# Mini-Ph0xx_00.net
KiCad netlist of a schematic drawn in Altium Designer
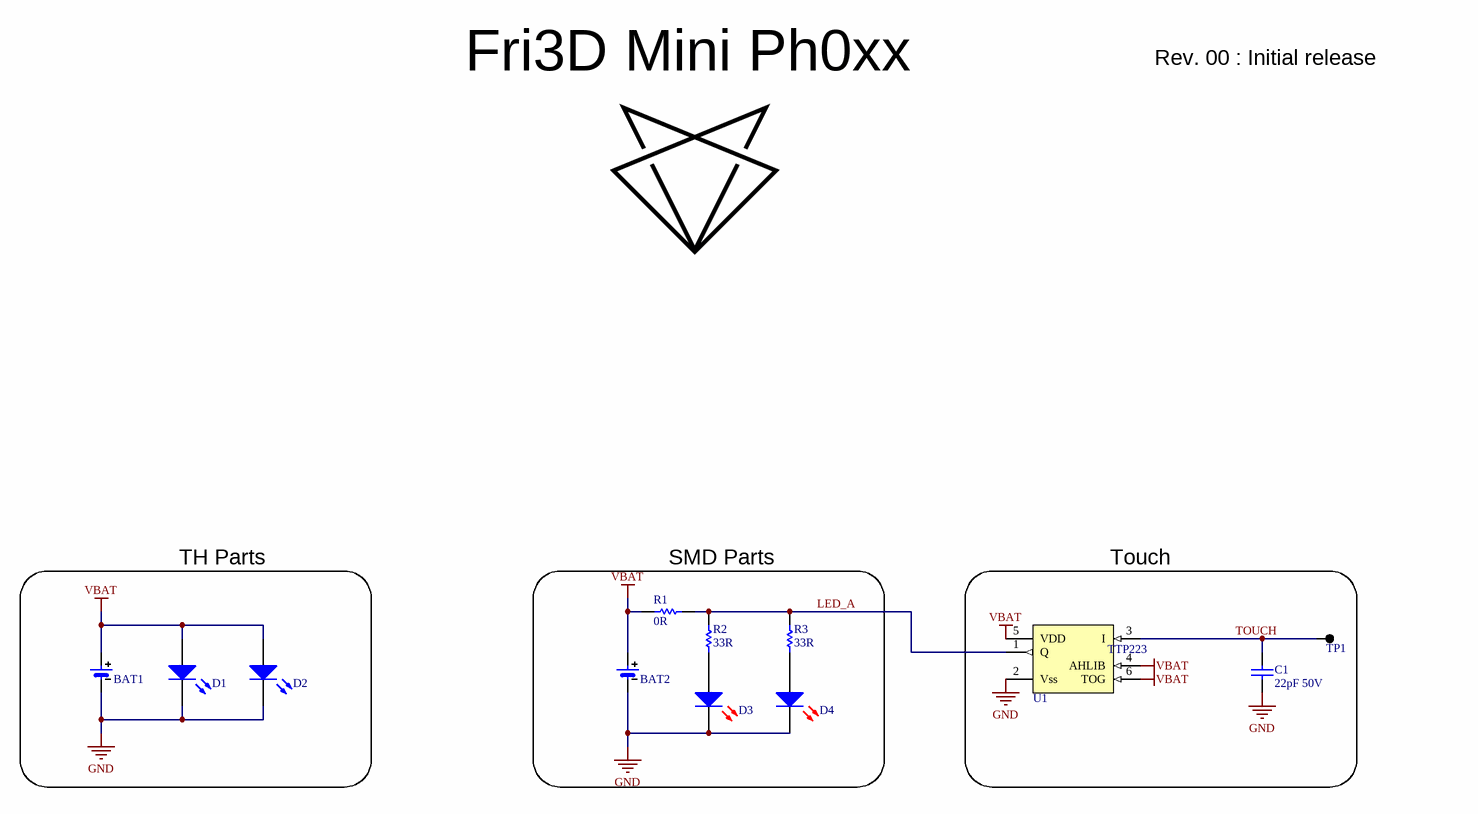
[diagram p0: Mini-Ph0xx_00.SchDoc]

(export (version "E")
  (design (tool "Eeschema 10.0.6"))
  (components
    (comp (ref "BAT1")
      (value "CR2032 Battery Holder")
      (footprint "BAT_CR2032")
      (description "=Description")
      (libsource (lib "Phyx_Components") (part "BAT_2"))
    )
    (comp (ref "BAT2")
      (value "CR2032 SMD Battery Holder")
      (footprint "BAT_CR2032_KEY_1060")
      (description "=Description")
      (libsource (lib "Phyx_Components") (part "BAT_2"))
    )
    (comp (ref "C1")
      (value "22pF 50V")
      (footprint "C1206_N")
      (description "Capacitor Ceramic")
      (fields (field (name "Comment") "CAP_CERAMIC"))
      (libsource (lib "Phyx_Components") (part "CAP_CERAMIC"))
    )
    (comp (ref "D1")
      (value "Default 5mm Blue LED")
      (footprint "LED_5MM_BL")
      (description "=Description")
      (libsource (lib "Phyx_Components") (part "LED_BLUE"))
    )
    (comp (ref "D2")
      (value "Default 5mm Blue LED")
      (footprint "LED_5MM_BL")
      (description "=Description")
      (libsource (lib "Phyx_Components") (part "LED_BLUE"))
    )
    (comp (ref "D3")
      (value "Default 0805 Red LED")
      (footprint "LED_0805_RD")
      (description "=Description")
      (libsource (lib "Phyx_Components") (part "LED_RED"))
    )
    (comp (ref "D4")
      (value "Default 0805 Red LED")
      (footprint "LED_0805_RD")
      (description "=Description")
      (libsource (lib "Phyx_Components") (part "LED_RED"))
    )
    (comp (ref "R1")
      (value "0R")
      (footprint "R1206")
      (fields (field (name "Comment") "RESISTOR"))
      (libsource (lib "Phyx_Components") (part "RESISTOR"))
    )
    (comp (ref "R2")
      (value "33R")
      (footprint "R1206")
      (fields (field (name "Comment") "RESISTOR"))
      (libsource (lib "Phyx_Components") (part "RESISTOR"))
    )
    (comp (ref "R3")
      (value "33R")
      (footprint "R1206")
      (fields (field (name "Comment") "RESISTOR"))
      (libsource (lib "Phyx_Components") (part "RESISTOR"))
    )
    (comp (ref "TP1")
      (value "TEST_PAD")
      (footprint "TP_0.8mm")
      (libsource (lib "Phyx_Components") (part "TEST_PAD"))
    )
    (comp (ref "U1")
      (value "Toggle dedicated touch IC")
      (footprint "SOT23-6")
      (description "=Description")
      (libsource (lib "Phyx_Components") (part "TTP223"))
    )
  )
  (nets
    (net (code "1") (name "/LED_A") (class "Default")
      (node (ref "R1") (pin "1") (pinfunction "1_1") (pintype "passive"))
      (node (ref "R2") (pin "1") (pinfunction "1_1") (pintype "passive"))
      (node (ref "R3") (pin "1") (pinfunction "1_1") (pintype "passive"))
      (node (ref "U1") (pin "1") (pinfunction "Q_1") (pintype "output"))
    )
    (net (code "2") (name "/TOUCH") (class "Default")
      (node (ref "C1") (pin "1") (pinfunction "1_1") (pintype "passive"))
      (node (ref "TP1") (pin "1") (pinfunction "1_1") (pintype "passive"))
      (node (ref "U1") (pin "3") (pinfunction "I_3") (pintype "input"))
    )
    (net (code "3") (name "GND") (class "Default")
      (node (ref "BAT1") (pin "2") (pinfunction "2_2") (pintype "passive"))
      (node (ref "BAT2") (pin "2") (pinfunction "2_2") (pintype "passive"))
      (node (ref "C1") (pin "2") (pinfunction "2_2") (pintype "passive"))
      (node (ref "D1") (pin "2") (pinfunction "K_2") (pintype "passive"))
      (node (ref "D2") (pin "2") (pinfunction "K_2") (pintype "passive"))
      (node (ref "D3") (pin "2") (pinfunction "K_2") (pintype "passive"))
      (node (ref "D4") (pin "2") (pinfunction "K_2") (pintype "passive"))
      (node (ref "U1") (pin "2") (pinfunction "Vss_2") (pintype "power_in"))
    )
    (net (code "4") (name "Net-(D3-A)") (class "Default")
      (node (ref "D3") (pin "1") (pinfunction "A_1") (pintype "passive"))
      (node (ref "R2") (pin "2") (pinfunction "2_2") (pintype "passive"))
    )
    (net (code "5") (name "Net-(D4-A)") (class "Default")
      (node (ref "D4") (pin "1") (pinfunction "A_1") (pintype "passive"))
      (node (ref "R3") (pin "2") (pinfunction "2_2") (pintype "passive"))
    )
    (net (code "6") (name "VBAT") (class "Default")
      (node (ref "BAT1") (pin "1") (pinfunction "1_1") (pintype "passive"))
      (node (ref "BAT2") (pin "1") (pinfunction "1_1") (pintype "passive"))
      (node (ref "D1") (pin "1") (pinfunction "A_1") (pintype "passive"))
      (node (ref "D2") (pin "1") (pinfunction "A_1") (pintype "passive"))
      (node (ref "R1") (pin "2") (pinfunction "2_2") (pintype "passive"))
      (node (ref "U1") (pin "4") (pinfunction "AHLIB_4") (pintype "input"))
      (node (ref "U1") (pin "5") (pinfunction "VDD_5") (pintype "power_in"))
      (node (ref "U1") (pin "6") (pinfunction "TOG_6") (pintype "input"))
    )
  )
)
